# SuperSmartSwitch.net
KiCad netlist of a schematic drawn in Altium Designer
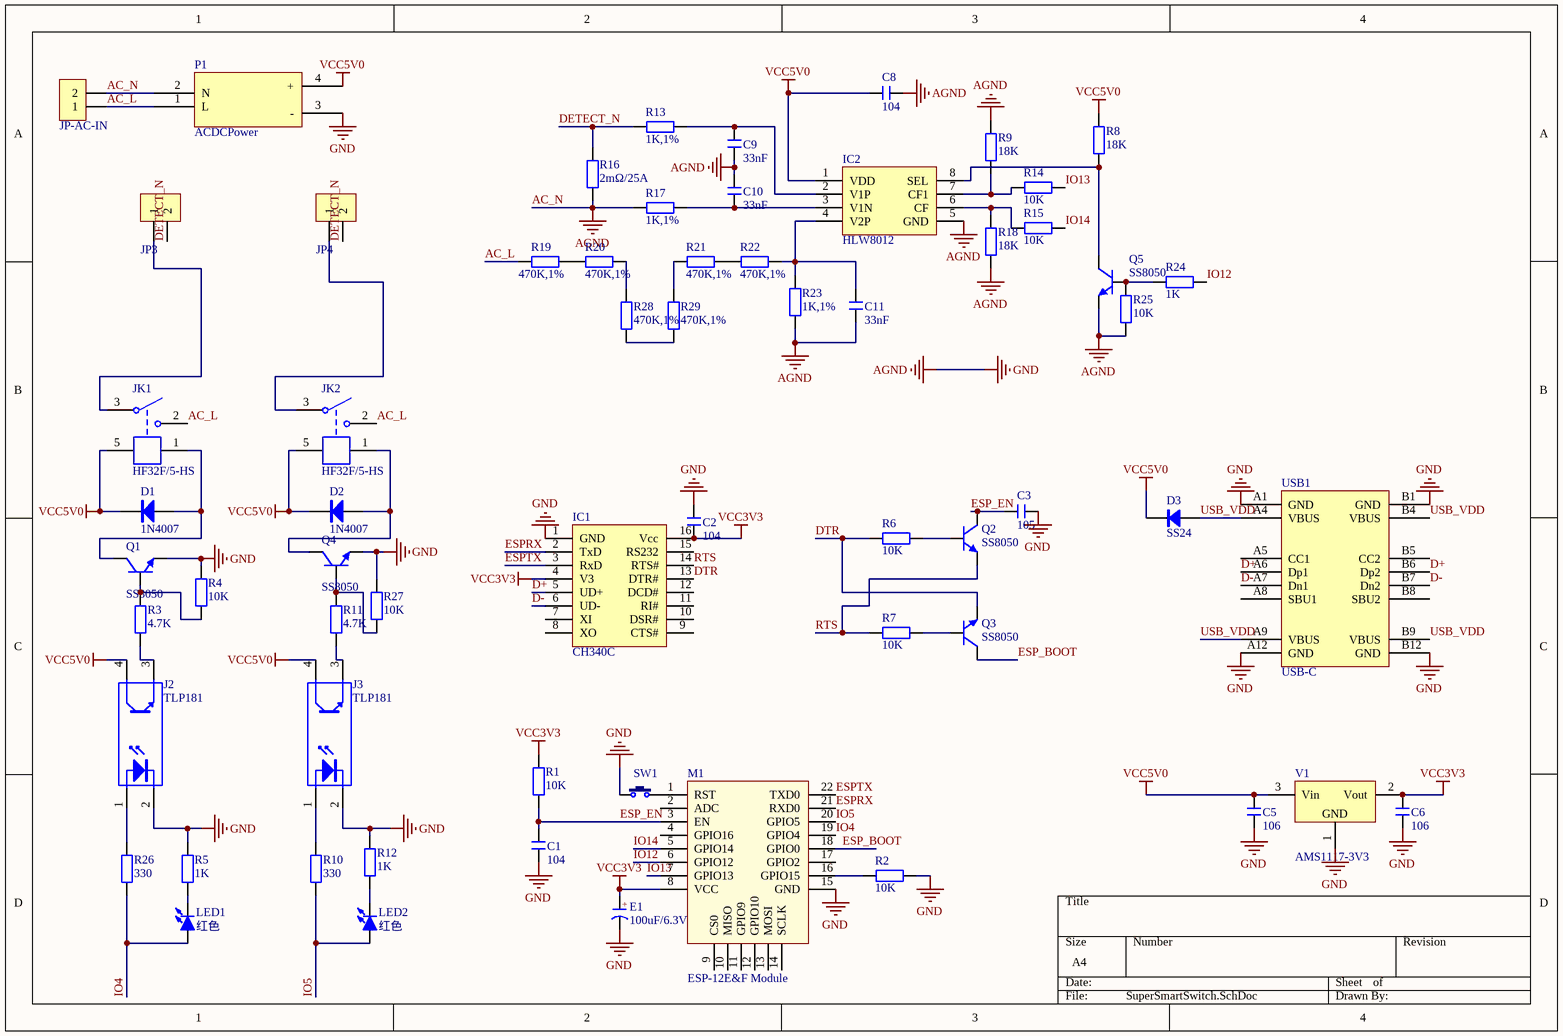
[diagram p0: SuperSmartSwitch.SchDoc]

(export (version "E")
  (design (tool "Eeschema 10.0.6"))
  (components
    (comp (ref "C1")
      (value "104")
      (footprint "C 0603_L")
      (description "无极性贴片电容")
      (fields (field (name "版权归属") "源创客"))
      (libsource (lib "3.1   - 电阻-电容-电感") (part "C"))
    )
    (comp (ref "C2")
      (value "104")
      (footprint "C 0603_L")
      (description "无极性贴片电容")
      (fields (field (name "版权归属") "源创客"))
      (libsource (lib "3.1   - 电阻-电容-电感") (part "C"))
    )
    (comp (ref "C3")
      (value "105")
      (footprint "C 0603_L")
      (description "无极性贴片电容")
      (fields (field (name "版权归属") "源创客"))
      (libsource (lib "3.1   - 电阻-电容-电感") (part "C"))
    )
    (comp (ref "C5")
      (value "106")
      (footprint "C 0603_L")
      (description "无极性贴片电容")
      (fields (field (name "版权归属") "源创客"))
      (libsource (lib "3.1   - 电阻-电容-电感") (part "C"))
    )
    (comp (ref "C6")
      (value "106")
      (footprint "C 0603_L")
      (description "无极性贴片电容")
      (fields (field (name "版权归属") "源创客"))
      (libsource (lib "3.1   - 电阻-电容-电感") (part "C"))
    )
    (comp (ref "C8")
      (value "104")
      (footprint "C 0603_L")
      (description "无极性贴片电容")
      (fields (field (name "版权归属") "源创客"))
      (libsource (lib "3.1   - 电阻-电容-电感") (part "C"))
    )
    (comp (ref "C9")
      (value "33nF")
      (footprint "C 0805_L")
      (description "无极性贴片电容")
      (fields (field (name "版权归属") "源创客"))
      (libsource (lib "3.1   - 电阻-电容-电感") (part "C"))
    )
    (comp (ref "C10")
      (value "33nF")
      (footprint "C 0805_L")
      (description "无极性贴片电容")
      (fields (field (name "版权归属") "源创客"))
      (libsource (lib "3.1   - 电阻-电容-电感") (part "C"))
    )
    (comp (ref "C11")
      (value "33nF")
      (footprint "C 0805_L")
      (description "无极性贴片电容")
      (fields (field (name "版权归属") "源创客"))
      (libsource (lib "3.1   - 电阻-电容-电感") (part "C"))
    )
    (comp (ref "D1")
      (value "1N4007")
      (footprint "SOD-123")
      (description "整流二极管")
      (fields (field (name "版权归属") "源创客"))
      (libsource (lib "8.1   - 二极管-整流桥") (part "1N4007"))
    )
    (comp (ref "D2")
      (value "1N4007")
      (footprint "SOD-123")
      (description "整流二极管")
      (fields (field (name "版权归属") "源创客"))
      (libsource (lib "8.1   - 二极管-整流桥") (part "1N4007"))
    )
    (comp (ref "D3")
      (value "SS24")
      (footprint "SMB")
      (description "肖特基二极管")
      (fields (field (name "版权归属") "源创客"))
      (libsource (lib "8.1   - 二极管-整流桥") (part "SS24"))
    )
    (comp (ref "E1")
      (value "100uF/6.3V")
      (footprint "CD A(3216)")
      (description "贴片钽电容")
      (fields (field (name "版权归属") "源创客"))
      (libsource (lib "3.1   - 电阻-电容-电感") (part "C-CD"))
    )
    (comp (ref "IC1")
      (value "CH340C")
      (footprint "SOP16_N")
      (description "串口转USB")
      (fields (field (name "版权归属") "源创客"))
      (libsource (lib "1.1   - IC芯片") (part "CH340G"))
    )
    (comp (ref "IC2")
      (value "HLW8012")
      (footprint "SOP8_M")
      (fields (field (name "版权归属") "源创客"))
      (libsource (lib "MyLib") (part "HLW8012"))
    )
    (comp (ref "J2")
      (value "TLP181")
      (footprint "SOP4_N")
      (description "光耦")
      (fields (field (name "版权归属") "源创客"))
      (libsource (lib "11.1 - 传感元件") (part "TLP181_1"))
    )
    (comp (ref "J3")
      (value "TLP181")
      (footprint "SOP4_N")
      (description "光耦")
      (fields (field (name "版权归属") "源创客"))
      (libsource (lib "11.1 - 传感元件") (part "TLP181_1"))
    )
    (comp (ref "JK1")
      (value "HF32F/5-HS")
      (footprint "JZC-32F_1H")
      (description "5V一组常开")
      (fields (field (name "版权归属") "源创客"))
      (libsource (lib "7.1   - 继电器") (part "HF32F/5-HS"))
    )
    (comp (ref "JK2")
      (value "HF32F/5-HS")
      (footprint "JZC-32F_1H")
      (description "5V一组常开")
      (fields (field (name "版权归属") "源创客"))
      (libsource (lib "7.1   - 继电器") (part "HF32F/5-HS"))
    )
    (comp (ref "JP-AC-IN")
      (value "HDR-1X2")
      (footprint "KF128-5.08-2P")
      (description "2P接插件")
      (fields (field (name "版权归属") "源创客"))
      (libsource (lib "") (part "Header 2_1"))
    )
    (comp (ref "JP3")
      (value "HDR-1X2")
      (footprint "KF128-5.08-2P")
      (description "2P接插件")
      (fields (field (name "版权归属") "源创客"))
      (libsource (lib "4.11 - 接插件-脚距5.08") (part "Header 2"))
    )
    (comp (ref "JP4")
      (value "HDR-1X2")
      (footprint "KF128-5.08-2P")
      (description "2P接插件")
      (fields (field (name "版权归属") "源创客"))
      (libsource (lib "4.11 - 接插件-脚距5.08") (part "Header 2"))
    )
    (comp (ref "LED1")
      (value "红色")
      (footprint "LED 0603B")
      (description "贴片LED")
      (fields (field (name "版权归属") "源创客"))
      (libsource (lib "9.1   - LED") (part "LED-SMD"))
    )
    (comp (ref "LED2")
      (value "红色")
      (footprint "LED 0603B")
      (description "贴片LED")
      (fields (field (name "版权归属") "源创客"))
      (libsource (lib "9.1   - LED") (part "LED-SMD"))
    )
    (comp (ref "M1")
      (value "ESP-12E&F Module")
      (footprint "ESP-12E&F Module")
      (libsource (lib "MyLib") (part "ESP-12E&F Module"))
    )
    (comp (ref "P1") (value "ACDCPower") (footprint "ADDC") (libsource (lib "MyLib") (part "ACDCPower")))
    (comp (ref "Q1")
      (value "SS8050")
      (footprint "SOT23-3N")
      (description "高频放大-NPN型")
      (fields (field (name "版权归属") "源创客"))
      (libsource (lib "6.2   - 三极管") (part "8050-SMD"))
    )
    (comp (ref "Q2")
      (value "SS8050")
      (footprint "SOT23-3N")
      (description "高频放大-NPN型")
      (fields (field (name "版权归属") "源创客"))
      (libsource (lib "6.2   - 三极管") (part "8050-SMD"))
    )
    (comp (ref "Q3")
      (value "SS8050")
      (footprint "SOT23-3N")
      (description "高频放大-NPN型")
      (fields (field (name "版权归属") "源创客"))
      (libsource (lib "6.2   - 三极管") (part "8050-SMD"))
    )
    (comp (ref "Q4")
      (value "SS8050")
      (footprint "SOT23-3N")
      (description "高频放大-NPN型")
      (fields (field (name "版权归属") "源创客"))
      (libsource (lib "6.2   - 三极管") (part "8050-SMD"))
    )
    (comp (ref "Q5")
      (value "SS8050")
      (footprint "SOT23-3N")
      (description "高频放大-NPN型")
      (fields (field (name "版权归属") "源创客"))
      (libsource (lib "6.2   - 三极管") (part "8050-SMD"))
    )
    (comp (ref "R1")
      (value "10K")
      (footprint "R 0603_L")
      (description "贴片电阻")
      (fields (field (name "版权归属") "源创客"))
      (libsource (lib "3.1   - 电阻-电容-电感") (part "R"))
    )
    (comp (ref "R2")
      (value "10K")
      (footprint "R 0603_L")
      (description "贴片电阻")
      (fields (field (name "版权归属") "源创客"))
      (libsource (lib "3.1   - 电阻-电容-电感") (part "R"))
    )
    (comp (ref "R3")
      (value "4.7K")
      (footprint "R 0603_L")
      (description "贴片电阻")
      (fields (field (name "版权归属") "源创客"))
      (libsource (lib "3.1   - 电阻-电容-电感") (part "R"))
    )
    (comp (ref "R4")
      (value "10K")
      (footprint "R 0603_L")
      (description "贴片电阻")
      (fields (field (name "版权归属") "源创客"))
      (libsource (lib "3.1   - 电阻-电容-电感") (part "R"))
    )
    (comp (ref "R5")
      (value "1K")
      (footprint "R 0603_L")
      (description "贴片电阻")
      (fields (field (name "版权归属") "源创客"))
      (libsource (lib "3.1   - 电阻-电容-电感") (part "R"))
    )
    (comp (ref "R6")
      (value "10K")
      (footprint "R 0603_L")
      (description "贴片电阻")
      (fields (field (name "版权归属") "源创客"))
      (libsource (lib "3.1   - 电阻-电容-电感") (part "R"))
    )
    (comp (ref "R7")
      (value "10K")
      (footprint "R 0603_L")
      (description "贴片电阻")
      (fields (field (name "版权归属") "源创客"))
      (libsource (lib "3.1   - 电阻-电容-电感") (part "R"))
    )
    (comp (ref "R8")
      (value "18K")
      (footprint "R 0603_L")
      (description "贴片电阻")
      (fields (field (name "版权归属") "源创客"))
      (libsource (lib "3.1   - 电阻-电容-电感") (part "R"))
    )
    (comp (ref "R9")
      (value "18K")
      (footprint "R 0603_L")
      (description "贴片电阻")
      (fields (field (name "版权归属") "源创客"))
      (libsource (lib "3.1   - 电阻-电容-电感") (part "R"))
    )
    (comp (ref "R10")
      (value "330")
      (footprint "R 0603_L")
      (description "贴片电阻")
      (fields (field (name "版权归属") "源创客"))
      (libsource (lib "3.1   - 电阻-电容-电感") (part "R"))
    )
    (comp (ref "R11")
      (value "4.7K")
      (footprint "R 0603_L")
      (description "贴片电阻")
      (fields (field (name "版权归属") "源创客"))
      (libsource (lib "3.1   - 电阻-电容-电感") (part "R"))
    )
    (comp (ref "R12")
      (value "1K")
      (footprint "R 0603_L")
      (description "贴片电阻")
      (fields (field (name "版权归属") "源创客"))
      (libsource (lib "3.1   - 电阻-电容-电感") (part "R"))
    )
    (comp (ref "R13")
      (value "1K,1%")
      (footprint "R 0805_L")
      (description "贴片电阻")
      (fields (field (name "版权归属") "源创客"))
      (libsource (lib "3.1   - 电阻-电容-电感") (part "R"))
    )
    (comp (ref "R14")
      (value "10K")
      (footprint "R 0603_L")
      (description "贴片电阻")
      (fields (field (name "版权归属") "源创客"))
      (libsource (lib "3.1   - 电阻-电容-电感") (part "R"))
    )
    (comp (ref "R15")
      (value "10K")
      (footprint "R 0603_L")
      (description "贴片电阻")
      (fields (field (name "版权归属") "源创客"))
      (libsource (lib "3.1   - 电阻-电容-电感") (part "R"))
    )
    (comp (ref "R16")
      (value "2mΩ/25A")
      (footprint "R 2512_L")
      (description "贴片电阻")
      (fields (field (name "版权归属") "源创客"))
      (libsource (lib "3.1   - 电阻-电容-电感") (part "R"))
    )
    (comp (ref "R17")
      (value "1K,1%")
      (footprint "R 0805_L")
      (description "贴片电阻")
      (fields (field (name "版权归属") "源创客"))
      (libsource (lib "3.1   - 电阻-电容-电感") (part "R"))
    )
    (comp (ref "R18")
      (value "18K")
      (footprint "R 0603_L")
      (description "贴片电阻")
      (fields (field (name "版权归属") "源创客"))
      (libsource (lib "3.1   - 电阻-电容-电感") (part "R"))
    )
    (comp (ref "R19")
      (value "470K,1%")
      (footprint "R 0805_L")
      (description "贴片电阻")
      (fields (field (name "版权归属") "源创客"))
      (libsource (lib "3.1   - 电阻-电容-电感") (part "R"))
    )
    (comp (ref "R20")
      (value "470K,1%")
      (footprint "R 0805_L")
      (description "贴片电阻")
      (fields (field (name "版权归属") "源创客"))
      (libsource (lib "3.1   - 电阻-电容-电感") (part "R"))
    )
    (comp (ref "R21")
      (value "470K,1%")
      (footprint "R 0805_L")
      (description "贴片电阻")
      (fields (field (name "版权归属") "源创客"))
      (libsource (lib "3.1   - 电阻-电容-电感") (part "R"))
    )
    (comp (ref "R22")
      (value "470K,1%")
      (footprint "R 0805_L")
      (description "贴片电阻")
      (fields (field (name "版权归属") "源创客"))
      (libsource (lib "3.1   - 电阻-电容-电感") (part "R"))
    )
    (comp (ref "R23")
      (value "1K,1%")
      (footprint "R 0805_L")
      (description "贴片电阻")
      (fields (field (name "版权归属") "源创客"))
      (libsource (lib "3.1   - 电阻-电容-电感") (part "R"))
    )
    (comp (ref "R24")
      (value "1K")
      (footprint "R 0603_L")
      (description "贴片电阻")
      (fields (field (name "版权归属") "源创客"))
      (libsource (lib "3.1   - 电阻-电容-电感") (part "R"))
    )
    (comp (ref "R25")
      (value "10K")
      (footprint "R 0603_L")
      (description "贴片电阻")
      (fields (field (name "版权归属") "源创客"))
      (libsource (lib "3.1   - 电阻-电容-电感") (part "R"))
    )
    (comp (ref "R26")
      (value "330")
      (footprint "R 0603_L")
      (description "贴片电阻")
      (fields (field (name "版权归属") "源创客"))
      (libsource (lib "3.1   - 电阻-电容-电感") (part "R"))
    )
    (comp (ref "R27")
      (value "10K")
      (footprint "R 0603_L")
      (description "贴片电阻")
      (fields (field (name "版权归属") "源创客"))
      (libsource (lib "3.1   - 电阻-电容-电感") (part "R"))
    )
    (comp (ref "R28")
      (value "470K,1%")
      (footprint "R 0805_L")
      (description "贴片电阻")
      (fields (field (name "版权归属") "源创客"))
      (libsource (lib "3.1   - 电阻-电容-电感") (part "R"))
    )
    (comp (ref "R29")
      (value "470K,1%")
      (footprint "R 0805_L")
      (description "贴片电阻")
      (fields (field (name "版权归属") "源创客"))
      (libsource (lib "3.1   - 电阻-电容-电感") (part "R"))
    )
    (comp (ref "SW1")
      (value "3x4x5")
      (footprint "TS3x4x2")
      (description "3x4轻触开关")
      (fields (field (name "版权归属") "源创客"))
      (libsource (lib "5.1   - 按键-开关") (part "TS 3x4"))
    )
    (comp (ref "USB1")
      (value "USB-C")
      (footprint "USB Type-C-16Pin_A")
      (description "USB-C型母接口")
      (fields (field (name "版权归属") "源创客"))
      (libsource (lib "4.1   - 接口类") (part "USB-C-16P"))
    )
    (comp (ref "V1")
      (value "AMS1117-3V3")
      (footprint "SOT223_N")
      (description "三端稳压芯片")
      (fields (field (name "版权归属") "源创客"))
      (libsource (lib "1.3   - 电源类芯片") (part "AMS1117"))
    )
  )
  (nets
    (net (code "1") (name "/AC_L") (class "Default")
      (node (ref "JK1") (pin "2") (pinfunction "2_2") (pintype "passive"))
      (node (ref "JK2") (pin "2") (pinfunction "2_2") (pintype "passive"))
      (node (ref "JP-AC-IN") (pin "1") (pinfunction "1_1") (pintype "passive"))
      (node (ref "P1") (pin "1") (pinfunction "L_1") (pintype "passive"))
      (node (ref "R19") (pin "2") (pinfunction "2_2") (pintype "passive"))
    )
    (net (code "2") (name "/D+") (class "Default")
      (node (ref "IC1") (pin "5") (pinfunction "UD+_5") (pintype "passive"))
      (node (ref "USB1") (pin "A6") (pinfunction "Dp1_A6") (pintype "passive"))
      (node (ref "USB1") (pin "B6") (pinfunction "Dp2_B6") (pintype "passive"))
    )
    (net (code "3") (name "/D-") (class "Default")
      (node (ref "IC1") (pin "6") (pinfunction "UD-_6") (pintype "passive"))
      (node (ref "USB1") (pin "A7") (pinfunction "Dn1_A7") (pintype "passive"))
      (node (ref "USB1") (pin "B7") (pinfunction "Dn2_B7") (pintype "passive"))
    )
    (net (code "4") (name "/DETECT_N") (class "Default")
      (node (ref "JP3") (pin "2") (pinfunction "2_2") (pintype "passive"))
      (node (ref "JP4") (pin "2") (pinfunction "2_2") (pintype "passive"))
      (node (ref "R13") (pin "2") (pinfunction "2_2") (pintype "passive"))
      (node (ref "R16") (pin "1") (pinfunction "1_1") (pintype "passive"))
    )
    (net (code "5") (name "/DTR") (class "Default")
      (node (ref "IC1") (pin "13") (pinfunction "DTR#_13") (pintype "passive"))
      (node (ref "Q3") (pin "2") (pinfunction "E_2") (pintype "passive"))
      (node (ref "R6") (pin "1") (pinfunction "1_1") (pintype "passive"))
    )
    (net (code "6") (name "/ESPRX") (class "Default")
      (node (ref "IC1") (pin "2") (pinfunction "TxD_2") (pintype "passive"))
      (node (ref "M1") (pin "21") (pinfunction "RXD0_21") (pintype "passive"))
    )
    (net (code "7") (name "/ESPTX") (class "Default")
      (node (ref "IC1") (pin "3") (pinfunction "RxD_3") (pintype "passive"))
      (node (ref "M1") (pin "22") (pinfunction "TXD0_22") (pintype "passive"))
    )
    (net (code "8") (name "/ESP_BOOT") (class "Default")
      (node (ref "M1") (pin "18") (pinfunction "GPIO0_18") (pintype "passive"))
      (node (ref "Q3") (pin "3") (pinfunction "C_3") (pintype "passive"))
    )
    (net (code "9") (name "/ESP_EN") (class "Default")
      (node (ref "C1") (pin "2") (pinfunction "2_2") (pintype "passive"))
      (node (ref "C3") (pin "2") (pinfunction "2_2") (pintype "passive"))
      (node (ref "M1") (pin "3") (pinfunction "EN_3") (pintype "passive"))
      (node (ref "Q2") (pin "3") (pinfunction "C_3") (pintype "passive"))
      (node (ref "R1") (pin "1") (pinfunction "1_1") (pintype "passive"))
    )
    (net (code "10") (name "/IO4") (class "Default")
      (node (ref "LED1") (pin "1") (pinfunction "A_1") (pintype "passive"))
      (node (ref "M1") (pin "19") (pinfunction "GPIO4_19") (pintype "passive"))
      (node (ref "R26") (pin "1") (pinfunction "1_1") (pintype "passive"))
    )
    (net (code "11") (name "/IO5") (class "Default")
      (node (ref "LED2") (pin "1") (pinfunction "A_1") (pintype "passive"))
      (node (ref "M1") (pin "20") (pinfunction "GPIO5_20") (pintype "passive"))
      (node (ref "R10") (pin "1") (pinfunction "1_1") (pintype "passive"))
    )
    (net (code "12") (name "/IO12") (class "Default")
      (node (ref "M1") (pin "6") (pinfunction "GPIO12_6") (pintype "passive"))
      (node (ref "R24") (pin "1") (pinfunction "1_1") (pintype "passive"))
    )
    (net (code "13") (name "/IO13") (class "Default")
      (node (ref "M1") (pin "7") (pinfunction "GPIO13_7") (pintype "passive"))
      (node (ref "R14") (pin "1") (pinfunction "1_1") (pintype "passive"))
    )
    (net (code "14") (name "/IO14") (class "Default")
      (node (ref "M1") (pin "5") (pinfunction "GPIO14_5") (pintype "passive"))
      (node (ref "R15") (pin "1") (pinfunction "1_1") (pintype "passive"))
    )
    (net (code "15") (name "/RTS") (class "Default")
      (node (ref "IC1") (pin "14") (pinfunction "RTS#_14") (pintype "passive"))
      (node (ref "Q2") (pin "2") (pinfunction "E_2") (pintype "passive"))
      (node (ref "R7") (pin "1") (pinfunction "1_1") (pintype "passive"))
    )
    (net (code "16") (name "/USB_VDD") (class "Default")
      (node (ref "D3") (pin "1") (pinfunction "A_1") (pintype "passive"))
      (node (ref "USB1") (pin "A4") (pinfunction "VBUS_A4") (pintype "passive"))
      (node (ref "USB1") (pin "A9") (pinfunction "VBUS_A9") (pintype "passive"))
      (node (ref "USB1") (pin "B4") (pinfunction "VBUS_B4") (pintype "passive"))
      (node (ref "USB1") (pin "B9") (pinfunction "VBUS_B9") (pintype "passive"))
    )
    (net (code "17") (name "AGND") (class "Default")
      (node (ref "C1") (pin "1") (pinfunction "1_1") (pintype "passive"))
      (node (ref "C10") (pin "2") (pinfunction "2_2") (pintype "passive"))
      (node (ref "C11") (pin "1") (pinfunction "1_1") (pintype "passive"))
      (node (ref "C2") (pin "1") (pinfunction "1_1") (pintype "passive"))
      (node (ref "C3") (pin "1") (pinfunction "1_1") (pintype "passive"))
      (node (ref "C5") (pin "1") (pinfunction "1_1") (pintype "passive"))
      (node (ref "C6") (pin "1") (pinfunction "1_1") (pintype "passive"))
      (node (ref "C8") (pin "2") (pinfunction "2_2") (pintype "passive"))
      (node (ref "C9") (pin "1") (pinfunction "1_1") (pintype "passive"))
      (node (ref "E1") (pin "2") (pinfunction "K_2") (pintype "passive"))
      (node (ref "IC1") (pin "1") (pinfunction "GND_1") (pintype "passive"))
      (node (ref "IC2") (pin "5") (pinfunction "GND_5") (pintype "passive"))
      (node (ref "J2") (pin "2") (pinfunction "K_2") (pintype "passive"))
      (node (ref "J3") (pin "2") (pinfunction "K_2") (pintype "passive"))
      (node (ref "JP-AC-IN") (pin "2") (pinfunction "2_2") (pintype "passive"))
      (node (ref "M1") (pin "15") (pinfunction "GND_15") (pintype "passive"))
      (node (ref "P1") (pin "2") (pinfunction "N_2") (pintype "passive"))
      (node (ref "P1") (pin "3") (pinfunction "-_3") (pintype "passive"))
      (node (ref "Q1") (pin "2") (pinfunction "E_2") (pintype "passive"))
      (node (ref "Q4") (pin "2") (pinfunction "E_2") (pintype "passive"))
      (node (ref "Q5") (pin "2") (pinfunction "E_2") (pintype "passive"))
      (node (ref "R12") (pin "1") (pinfunction "1_1") (pintype "passive"))
      (node (ref "R16") (pin "2") (pinfunction "2_2") (pintype "passive"))
      (node (ref "R17") (pin "2") (pinfunction "2_2") (pintype "passive"))
      (node (ref "R18") (pin "2") (pinfunction "2_2") (pintype "passive"))
      (node (ref "R2") (pin "1") (pinfunction "1_1") (pintype "passive"))
      (node (ref "R23") (pin "1") (pinfunction "1_1") (pintype "passive"))
      (node (ref "R25") (pin "2") (pinfunction "2_2") (pintype "passive"))
      (node (ref "R27") (pin "2") (pinfunction "2_2") (pintype "passive"))
      (node (ref "R4") (pin "2") (pinfunction "2_2") (pintype "passive"))
      (node (ref "R5") (pin "1") (pinfunction "1_1") (pintype "passive"))
      (node (ref "R9") (pin "1") (pinfunction "1_1") (pintype "passive"))
      (node (ref "SW1") (pin "1") (pinfunction "1_1") (pintype "passive"))
      (node (ref "USB1") (pin "A1") (pinfunction "GND_A1") (pintype "passive"))
      (node (ref "USB1") (pin "A12") (pinfunction "GND_A12") (pintype "passive"))
      (node (ref "USB1") (pin "B1") (pinfunction "GND_B1") (pintype "passive"))
      (node (ref "USB1") (pin "B12") (pinfunction "GND_B12") (pintype "passive"))
      (node (ref "V1") (pin "1") (pinfunction "GND_1") (pintype "passive"))
    )
    (net (code "18") (name "Net-(D1-A)") (class "Default")
      (node (ref "D1") (pin "1") (pinfunction "A_1") (pintype "passive"))
      (node (ref "JK1") (pin "1") (pinfunction "1_1") (pintype "passive"))
      (node (ref "Q1") (pin "3") (pinfunction "C_3") (pintype "passive"))
    )
    (net (code "19") (name "Net-(D2-A)") (class "Default")
      (node (ref "D2") (pin "1") (pinfunction "A_1") (pintype "passive"))
      (node (ref "JK2") (pin "1") (pinfunction "1_1") (pintype "passive"))
      (node (ref "Q4") (pin "3") (pinfunction "C_3") (pintype "passive"))
    )
    (net (code "20") (name "Net-(IC2-CF)") (class "Default")
      (node (ref "IC2") (pin "6") (pinfunction "CF_6") (pintype "passive"))
      (node (ref "R15") (pin "2") (pinfunction "2_2") (pintype "passive"))
      (node (ref "R18") (pin "1") (pinfunction "1_1") (pintype "passive"))
    )
    (net (code "21") (name "Net-(IC2-CF1)") (class "Default")
      (node (ref "IC2") (pin "7") (pinfunction "CF1_7") (pintype "passive"))
      (node (ref "R14") (pin "2") (pinfunction "2_2") (pintype "passive"))
      (node (ref "R9") (pin "2") (pinfunction "2_2") (pintype "passive"))
    )
    (net (code "22") (name "Net-(IC2-SEL)") (class "Default")
      (node (ref "IC2") (pin "8") (pinfunction "SEL_8") (pintype "passive"))
      (node (ref "Q5") (pin "3") (pinfunction "C_3") (pintype "passive"))
      (node (ref "R8") (pin "2") (pinfunction "2_2") (pintype "passive"))
    )
    (net (code "23") (name "Net-(IC2-V1N)") (class "Default")
      (node (ref "C10") (pin "1") (pinfunction "1_1") (pintype "passive"))
      (node (ref "IC2") (pin "3") (pinfunction "V1N_3") (pintype "passive"))
      (node (ref "R17") (pin "1") (pinfunction "1_1") (pintype "passive"))
    )
    (net (code "24") (name "Net-(IC2-V1P)") (class "Default")
      (node (ref "C9") (pin "2") (pinfunction "2_2") (pintype "passive"))
      (node (ref "IC2") (pin "2") (pinfunction "V1P_2") (pintype "passive"))
      (node (ref "R13") (pin "1") (pinfunction "1_1") (pintype "passive"))
    )
    (net (code "25") (name "Net-(IC2-V2P)") (class "Default")
      (node (ref "C11") (pin "2") (pinfunction "2_2") (pintype "passive"))
      (node (ref "IC2") (pin "4") (pinfunction "V2P_4") (pintype "passive"))
      (node (ref "R22") (pin "1") (pinfunction "1_1") (pintype "passive"))
      (node (ref "R23") (pin "2") (pinfunction "2_2") (pintype "passive"))
    )
    (net (code "26") (name "Net-(J2-A)") (class "Default")
      (node (ref "J2") (pin "1") (pinfunction "A_1") (pintype "passive"))
      (node (ref "R26") (pin "2") (pinfunction "2_2") (pintype "passive"))
    )
    (net (code "27") (name "Net-(J2-E)") (class "Default")
      (node (ref "J2") (pin "3") (pinfunction "E_3") (pintype "passive"))
      (node (ref "R3") (pin "2") (pinfunction "2_2") (pintype "passive"))
    )
    (net (code "28") (name "Net-(J3-A)") (class "Default")
      (node (ref "J3") (pin "1") (pinfunction "A_1") (pintype "passive"))
      (node (ref "R10") (pin "2") (pinfunction "2_2") (pintype "passive"))
    )
    (net (code "29") (name "Net-(J3-E)") (class "Default")
      (node (ref "J3") (pin "3") (pinfunction "E_3") (pintype "passive"))
      (node (ref "R11") (pin "2") (pinfunction "2_2") (pintype "passive"))
    )
    (net (code "30") (name "Net-(JK1-Pad3)") (class "Default")
      (node (ref "JK1") (pin "3") (pinfunction "3_3") (pintype "passive"))
      (node (ref "JP3") (pin "1") (pinfunction "1_1") (pintype "passive"))
    )
    (net (code "31") (name "Net-(JK2-Pad3)") (class "Default")
      (node (ref "JK2") (pin "3") (pinfunction "3_3") (pintype "passive"))
      (node (ref "JP4") (pin "1") (pinfunction "1_1") (pintype "passive"))
    )
    (net (code "32") (name "Net-(LED1-K)") (class "Default")
      (node (ref "LED1") (pin "2") (pinfunction "K_2") (pintype "passive"))
      (node (ref "R5") (pin "2") (pinfunction "2_2") (pintype "passive"))
    )
    (net (code "33") (name "Net-(LED2-K)") (class "Default")
      (node (ref "LED2") (pin "2") (pinfunction "K_2") (pintype "passive"))
      (node (ref "R12") (pin "2") (pinfunction "2_2") (pintype "passive"))
    )
    (net (code "34") (name "Net-(M1-GPIO15)") (class "Default")
      (node (ref "M1") (pin "16") (pinfunction "GPIO15_16") (pintype "passive"))
      (node (ref "R2") (pin "2") (pinfunction "2_2") (pintype "passive"))
    )
    (net (code "35") (name "Net-(M1-RST)") (class "Default")
      (node (ref "M1") (pin "1") (pinfunction "RST_1") (pintype "passive"))
      (node (ref "SW1") (pin "2") (pinfunction "2_2") (pintype "passive"))
    )
    (net (code "36") (name "Net-(Q1-B)") (class "Default")
      (node (ref "Q1") (pin "1") (pinfunction "B_1") (pintype "passive"))
      (node (ref "R3") (pin "1") (pinfunction "1_1") (pintype "passive"))
      (node (ref "R4") (pin "1") (pinfunction "1_1") (pintype "passive"))
    )
    (net (code "37") (name "Net-(Q2-B)") (class "Default")
      (node (ref "Q2") (pin "1") (pinfunction "B_1") (pintype "passive"))
      (node (ref "R6") (pin "2") (pinfunction "2_2") (pintype "passive"))
    )
    (net (code "38") (name "Net-(Q3-B)") (class "Default")
      (node (ref "Q3") (pin "1") (pinfunction "B_1") (pintype "passive"))
      (node (ref "R7") (pin "2") (pinfunction "2_2") (pintype "passive"))
    )
    (net (code "39") (name "Net-(Q4-B)") (class "Default")
      (node (ref "Q4") (pin "1") (pinfunction "B_1") (pintype "passive"))
      (node (ref "R11") (pin "1") (pinfunction "1_1") (pintype "passive"))
      (node (ref "R27") (pin "1") (pinfunction "1_1") (pintype "passive"))
    )
    (net (code "40") (name "Net-(Q5-B)") (class "Default")
      (node (ref "Q5") (pin "1") (pinfunction "B_1") (pintype "passive"))
      (node (ref "R24") (pin "2") (pinfunction "2_2") (pintype "passive"))
      (node (ref "R25") (pin "1") (pinfunction "1_1") (pintype "passive"))
    )
    (net (code "41") (name "Net-(R19-Pad1)") (class "Default")
      (node (ref "R19") (pin "1") (pinfunction "1_1") (pintype "passive"))
      (node (ref "R20") (pin "2") (pinfunction "2_2") (pintype "passive"))
    )
    (net (code "42") (name "Net-(R20-Pad1)") (class "Default")
      (node (ref "R20") (pin "1") (pinfunction "1_1") (pintype "passive"))
      (node (ref "R28") (pin "1") (pinfunction "1_1") (pintype "passive"))
    )
    (net (code "43") (name "Net-(R21-Pad1)") (class "Default")
      (node (ref "R21") (pin "1") (pinfunction "1_1") (pintype "passive"))
      (node (ref "R22") (pin "2") (pinfunction "2_2") (pintype "passive"))
    )
    (net (code "44") (name "Net-(R21-Pad2)") (class "Default")
      (node (ref "R21") (pin "2") (pinfunction "2_2") (pintype "passive"))
      (node (ref "R29") (pin "1") (pinfunction "1_1") (pintype "passive"))
    )
    (net (code "45") (name "Net-(R28-Pad2)") (class "Default")
      (node (ref "R28") (pin "2") (pinfunction "2_2") (pintype "passive"))
      (node (ref "R29") (pin "2") (pinfunction "2_2") (pintype "passive"))
    )
    (net (code "46") (name "VCC3V3") (class "Default")
      (node (ref "C2") (pin "2") (pinfunction "2_2") (pintype "passive"))
      (node (ref "C6") (pin "2") (pinfunction "2_2") (pintype "passive"))
      (node (ref "E1") (pin "1") (pinfunction "A_1") (pintype "passive"))
      (node (ref "IC1") (pin "16") (pinfunction "Vcc_16") (pintype "passive"))
      (node (ref "IC1") (pin "4") (pinfunction "V3_4") (pintype "passive"))
      (node (ref "M1") (pin "8") (pinfunction "VCC_8") (pintype "passive"))
      (node (ref "R1") (pin "2") (pinfunction "2_2") (pintype "passive"))
      (node (ref "V1") (pin "2") (pinfunction "Vout_2") (pintype "passive"))
    )
    (net (code "47") (name "VCC5V0") (class "Default")
      (node (ref "C5") (pin "2") (pinfunction "2_2") (pintype "passive"))
      (node (ref "C8") (pin "1") (pinfunction "1_1") (pintype "passive"))
      (node (ref "D1") (pin "2") (pinfunction "K_2") (pintype "passive"))
      (node (ref "D2") (pin "2") (pinfunction "K_2") (pintype "passive"))
      (node (ref "D3") (pin "2") (pinfunction "K_2") (pintype "passive"))
      (node (ref "IC2") (pin "1") (pinfunction "VDD_1") (pintype "passive"))
      (node (ref "J2") (pin "4") (pinfunction "C_4") (pintype "passive"))
      (node (ref "J3") (pin "4") (pinfunction "C_4") (pintype "passive"))
      (node (ref "JK1") (pin "5") (pinfunction "5_5") (pintype "passive"))
      (node (ref "JK2") (pin "5") (pinfunction "5_5") (pintype "passive"))
      (node (ref "P1") (pin "4") (pinfunction "+_4") (pintype "passive"))
      (node (ref "R8") (pin "1") (pinfunction "1_1") (pintype "passive"))
      (node (ref "V1") (pin "3") (pinfunction "Vin_3") (pintype "passive"))
    )
    (net (code "48") (name "unconnected-(IC1-CTS#-Pad9)") (class "Default")
      (node (ref "IC1") (pin "9") (pinfunction "CTS#_9") (pintype "passive"))
    )
    (net (code "49") (name "unconnected-(IC1-DCD#-Pad12)") (class "Default")
      (node (ref "IC1") (pin "12") (pinfunction "DCD#_12") (pintype "passive"))
    )
    (net (code "50") (name "unconnected-(IC1-DSR#-Pad10)") (class "Default")
      (node (ref "IC1") (pin "10") (pinfunction "DSR#_10") (pintype "passive"))
    )
    (net (code "51") (name "unconnected-(IC1-RI#-Pad11)") (class "Default")
      (node (ref "IC1") (pin "11") (pinfunction "RI#_11") (pintype "passive"))
    )
    (net (code "52") (name "unconnected-(IC1-RS232-Pad15)") (class "Default")
      (node (ref "IC1") (pin "15") (pinfunction "RS232_15") (pintype "passive"))
    )
    (net (code "53") (name "unconnected-(IC1-XI-Pad7)") (class "Default")
      (node (ref "IC1") (pin "7") (pinfunction "XI_7") (pintype "passive"))
    )
    (net (code "54") (name "unconnected-(IC1-XO-Pad8)") (class "Default")
      (node (ref "IC1") (pin "8") (pinfunction "XO_8") (pintype "passive"))
    )
    (net (code "55") (name "unconnected-(M1-ADC-Pad2)") (class "Default")
      (node (ref "M1") (pin "2") (pinfunction "ADC_2") (pintype "passive"))
    )
    (net (code "56") (name "unconnected-(M1-CS0-Pad9)") (class "Default")
      (node (ref "M1") (pin "9") (pinfunction "CS0_9") (pintype "passive"))
    )
    (net (code "57") (name "unconnected-(M1-GPIO2-Pad17)") (class "Default")
      (node (ref "M1") (pin "17") (pinfunction "GPIO2_17") (pintype "passive"))
    )
    (net (code "58") (name "unconnected-(M1-GPIO9-Pad11)") (class "Default")
      (node (ref "M1") (pin "11") (pinfunction "GPIO9_11") (pintype "passive"))
    )
    (net (code "59") (name "unconnected-(M1-GPIO10-Pad12)") (class "Default")
      (node (ref "M1") (pin "12") (pinfunction "GPIO10_12") (pintype "passive"))
    )
    (net (code "60") (name "unconnected-(M1-GPIO16-Pad4)") (class "Default")
      (node (ref "M1") (pin "4") (pinfunction "GPIO16_4") (pintype "passive"))
    )
    (net (code "61") (name "unconnected-(M1-MISO-Pad10)") (class "Default")
      (node (ref "M1") (pin "10") (pinfunction "MISO_10") (pintype "passive"))
    )
    (net (code "62") (name "unconnected-(M1-MOSI-Pad13)") (class "Default")
      (node (ref "M1") (pin "13") (pinfunction "MOSI_13") (pintype "passive"))
    )
    (net (code "63") (name "unconnected-(M1-SCLK-Pad14)") (class "Default")
      (node (ref "M1") (pin "14") (pinfunction "SCLK_14") (pintype "passive"))
    )
    (net (code "64") (name "unconnected-(USB1-CC1-PadA5)") (class "Default")
      (node (ref "USB1") (pin "A5") (pinfunction "CC1_A5") (pintype "passive"))
    )
    (net (code "65") (name "unconnected-(USB1-CC2-PadB5)") (class "Default")
      (node (ref "USB1") (pin "B5") (pinfunction "CC2_B5") (pintype "passive"))
    )
    (net (code "66") (name "unconnected-(USB1-SBU1-PadA8)") (class "Default")
      (node (ref "USB1") (pin "A8") (pinfunction "SBU1_A8") (pintype "passive"))
    )
    (net (code "67") (name "unconnected-(USB1-SBU2-PadB8)") (class "Default")
      (node (ref "USB1") (pin "B8") (pinfunction "SBU2_B8") (pintype "passive"))
    )
  )
)
